# Sheet2.net
KiCad netlist of a schematic drawn in Altium Designer
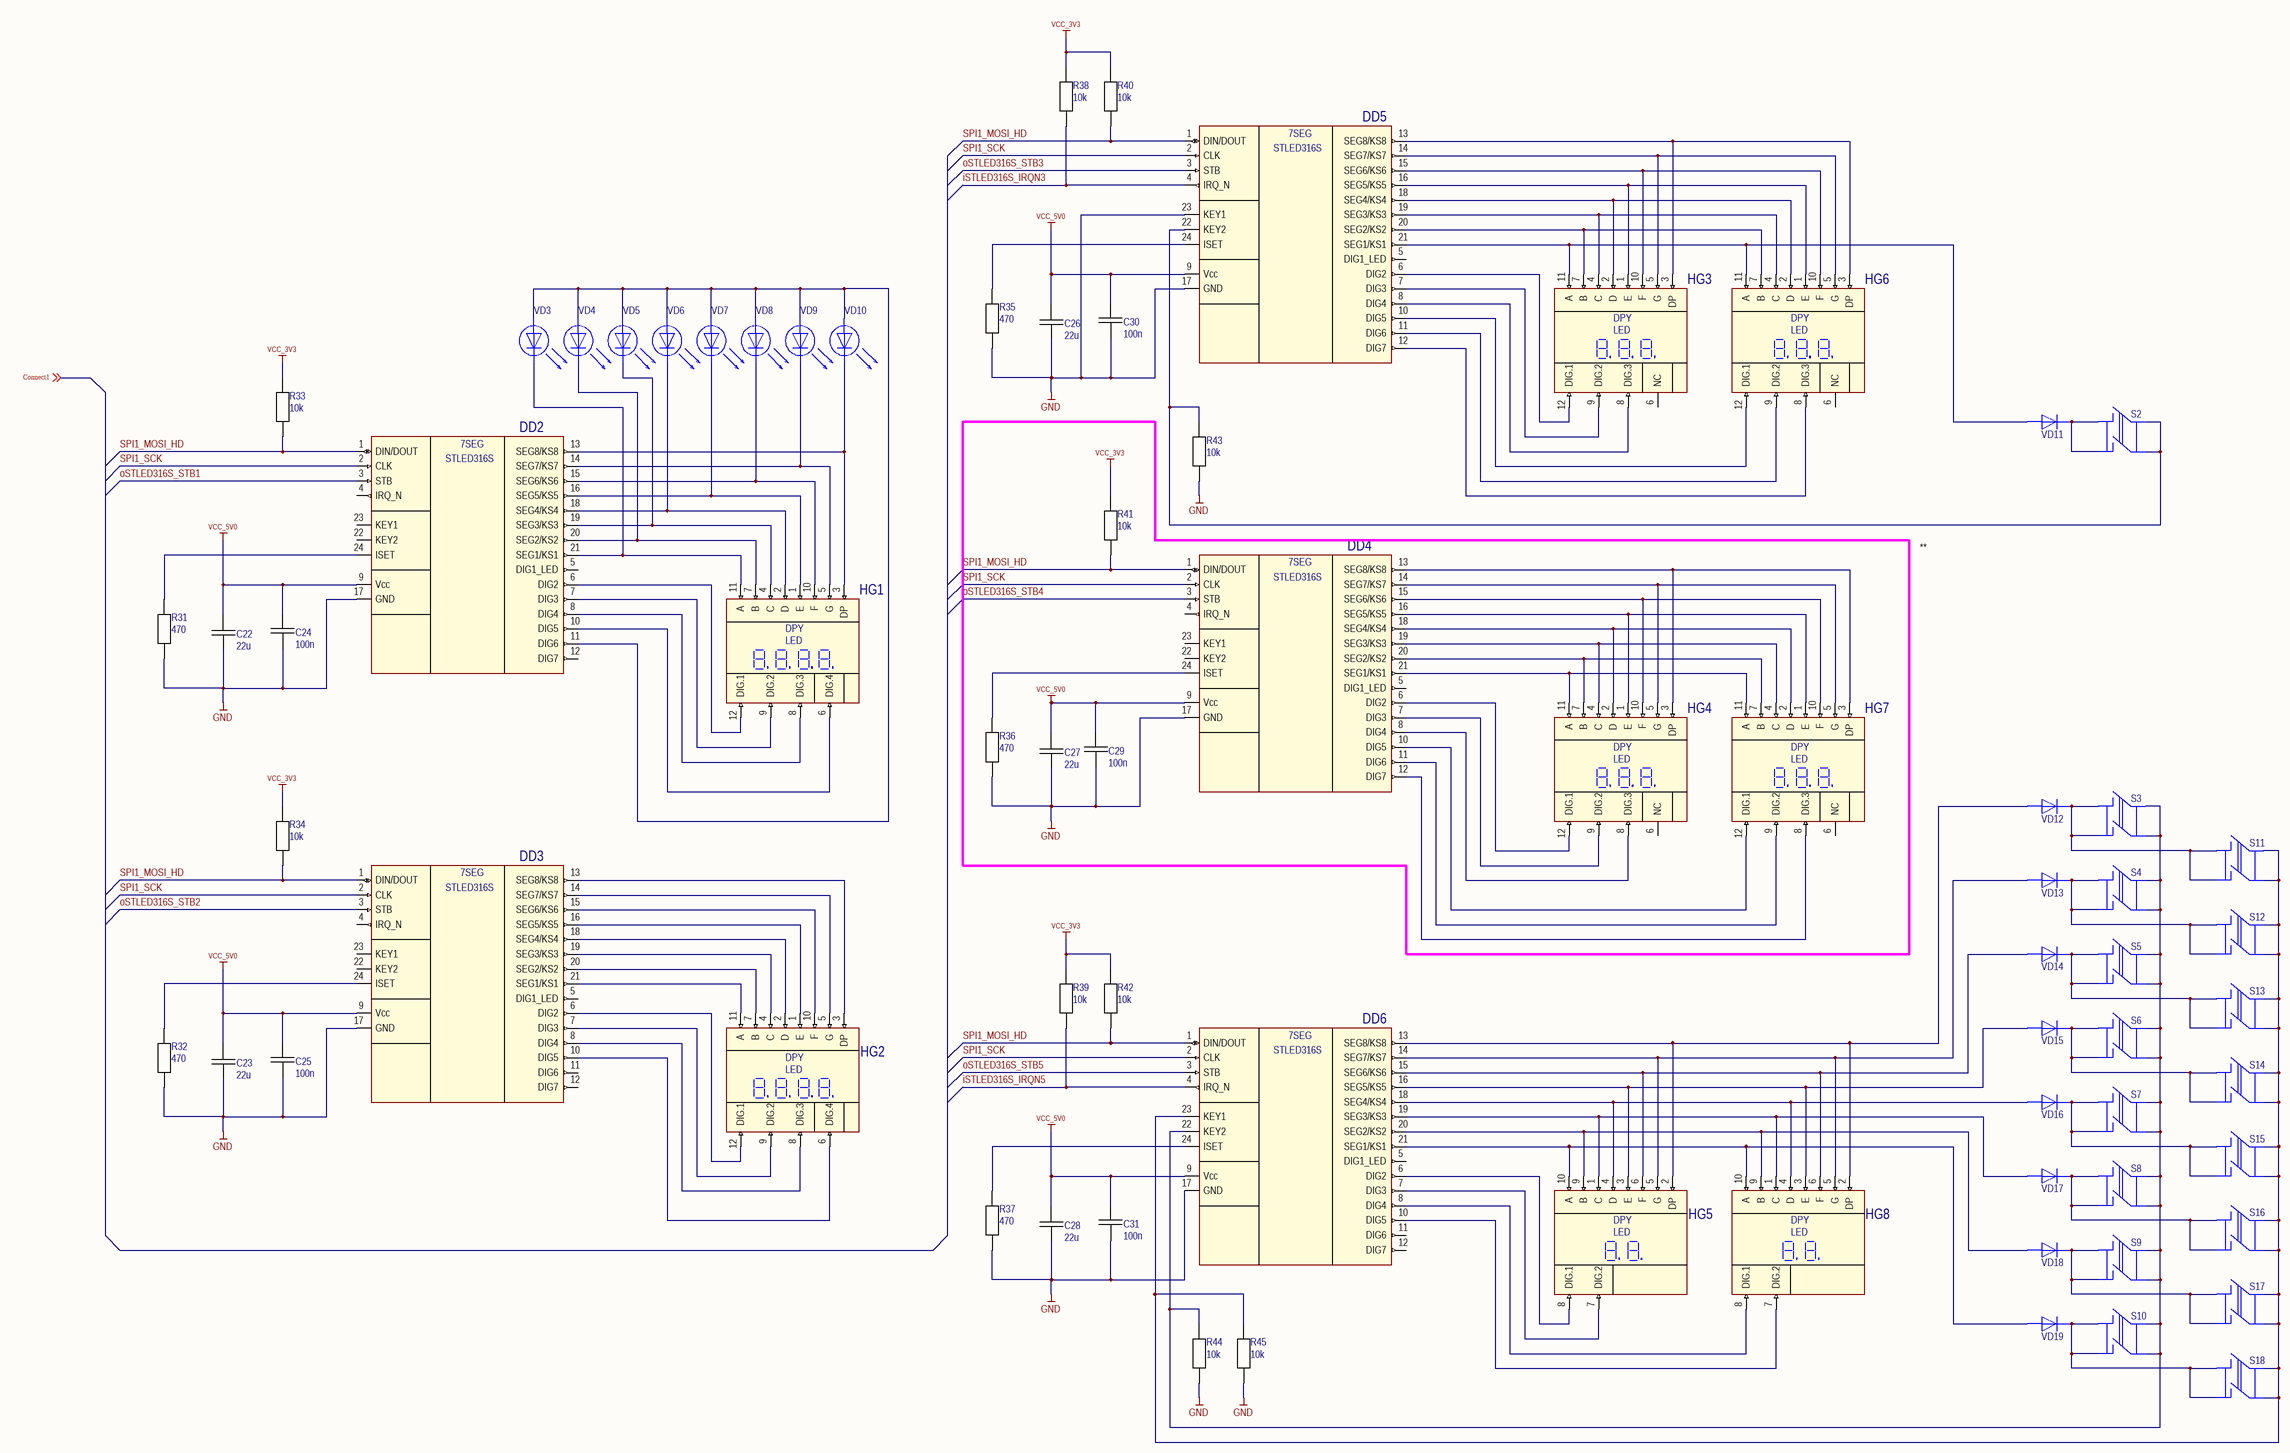
[diagram p0: Sheet2.SchDoc]

(export (version "E")
  (design (tool "Eeschema 10.0.6"))
  (components
    (comp (ref "C22")
      (value "22u")
      (footprint "CAPACITOR_1206")
      (libsource (lib "Библиотека элементов") (part "Capacitor_1206"))
    )
    (comp (ref "C23")
      (value "22u")
      (footprint "CAPACITOR_1206")
      (libsource (lib "Библиотека элементов") (part "Capacitor_1206"))
    )
    (comp (ref "C24")
      (value "100n")
      (footprint "Capacitor_0805")
      (libsource (lib "Библиотека элементов") (part "Capacitor_0805"))
    )
    (comp (ref "C25")
      (value "100n")
      (footprint "Capacitor_0805")
      (libsource (lib "Библиотека элементов") (part "Capacitor_0805"))
    )
    (comp (ref "C26")
      (value "22u")
      (footprint "CAPACITOR_1206")
      (libsource (lib "Библиотека элементов") (part "Capacitor_1206"))
    )
    (comp (ref "C27")
      (value "22u")
      (footprint "CAPACITOR_1206")
      (libsource (lib "Библиотека элементов") (part "Capacitor_1206"))
    )
    (comp (ref "C28")
      (value "22u")
      (footprint "CAPACITOR_1206")
      (libsource (lib "Библиотека элементов") (part "Capacitor_1206"))
    )
    (comp (ref "C29")
      (value "100n")
      (footprint "Capacitor_0805")
      (libsource (lib "Библиотека элементов") (part "Capacitor_0805"))
    )
    (comp (ref "C30")
      (value "100n")
      (footprint "Capacitor_0805")
      (libsource (lib "Библиотека элементов") (part "Capacitor_0805"))
    )
    (comp (ref "C31")
      (value "100n")
      (footprint "Capacitor_0805")
      (libsource (lib "Библиотека элементов") (part "Capacitor_0805"))
    )
    (comp (ref "DD2")
      (value "STLED316S")
      (footprint "SO-24")
      (libsource (lib "Библиотека элементов") (part "STLED316S"))
    )
    (comp (ref "DD3")
      (value "STLED316S")
      (footprint "SO-24")
      (libsource (lib "Библиотека элементов") (part "STLED316S"))
    )
    (comp (ref "DD4")
      (value "STLED316S")
      (footprint "SO-24")
      (libsource (lib "Библиотека элементов") (part "STLED316S"))
    )
    (comp (ref "DD5")
      (value "STLED316S")
      (footprint "SO-24")
      (libsource (lib "Библиотека элементов") (part "STLED316S"))
    )
    (comp (ref "DD6")
      (value "STLED316S")
      (footprint "SO-24")
      (libsource (lib "Библиотека элементов") (part "STLED316S"))
    )
    (comp (ref "HG1")
      (value "FYQ-5641BG-21")
      (footprint "FYQ-5641BG-21")
      (libsource (lib "Библиотека элементов") (part "FYQ-5641BG-21"))
    )
    (comp (ref "HG2")
      (value "FYQ-5641BG-21")
      (footprint "FYQ-5641BG-21")
      (libsource (lib "Библиотека элементов") (part "FYQ-5641BG-21"))
    )
    (comp (ref "HG3")
      (value "FYT-5631Bx")
      (footprint "FYT-5631Bx")
      (libsource (lib "Библиотека элементов") (part "FYT-5631Bx"))
    )
    (comp (ref "HG4") (value "FYT-5631Bx") (libsource (lib "Библиотека элементов") (part "FYT-5631Bx")))
    (comp (ref "HG5")
      (value "FYD-5621Bx")
      (footprint "FYD-5621Bx")
      (libsource (lib "Библиотека элементов") (part "FYD-5621Bx"))
    )
    (comp (ref "HG6")
      (value "FYT-5631Bx")
      (footprint "FYT-5631Bx")
      (libsource (lib "Библиотека элементов") (part "FYT-5631Bx"))
    )
    (comp (ref "HG7") (value "FYT-5631Bx") (libsource (lib "Библиотека элементов") (part "FYT-5631Bx")))
    (comp (ref "HG8")
      (value "FYD-5621Bx")
      (footprint "FYD-5621Bx")
      (libsource (lib "Библиотека элементов") (part "FYD-5621Bx"))
    )
    (comp (ref "R31")
      (value "470")
      (footprint "RESISTOR_SMD0805")
      (libsource (lib "Библиотека элементов") (part "Resistor_0805"))
    )
    (comp (ref "R32")
      (value "470")
      (footprint "RESISTOR_SMD0805")
      (libsource (lib "Библиотека элементов") (part "Resistor_0805"))
    )
    (comp (ref "R33")
      (value "10k")
      (footprint "RESISTOR_SMD0805")
      (libsource (lib "Библиотека элементов") (part "Resistor_0805"))
    )
    (comp (ref "R34")
      (value "10k")
      (footprint "RESISTOR_SMD0805")
      (libsource (lib "Библиотека элементов") (part "Resistor_0805"))
    )
    (comp (ref "R35")
      (value "470")
      (footprint "RESISTOR_SMD0805")
      (libsource (lib "Библиотека элементов") (part "Resistor_0805"))
    )
    (comp (ref "R36")
      (value "470")
      (footprint "RESISTOR_SMD0805")
      (libsource (lib "Библиотека элементов") (part "Resistor_0805"))
    )
    (comp (ref "R37")
      (value "470")
      (footprint "RESISTOR_SMD0805")
      (libsource (lib "Библиотека элементов") (part "Resistor_0805"))
    )
    (comp (ref "R38")
      (value "10k")
      (footprint "RESISTOR_SMD0805")
      (libsource (lib "Библиотека элементов") (part "Resistor_0805"))
    )
    (comp (ref "R39")
      (value "10k")
      (footprint "RESISTOR_SMD0805")
      (libsource (lib "Библиотека элементов") (part "Resistor_0805"))
    )
    (comp (ref "R40")
      (value "10k")
      (footprint "RESISTOR_SMD0805")
      (libsource (lib "Библиотека элементов") (part "Resistor_0805"))
    )
    (comp (ref "R41")
      (value "10k")
      (footprint "RESISTOR_SMD0805")
      (libsource (lib "Библиотека элементов") (part "Resistor_0805"))
    )
    (comp (ref "R42")
      (value "10k")
      (footprint "RESISTOR_SMD0805")
      (libsource (lib "Библиотека элементов") (part "Resistor_0805"))
    )
    (comp (ref "R43")
      (value "10k")
      (footprint "RESISTOR_SMD0805")
      (libsource (lib "Библиотека элементов") (part "Resistor_0805"))
    )
    (comp (ref "R44")
      (value "10k")
      (footprint "RESISTOR_SMD0805")
      (libsource (lib "Библиотека элементов") (part "Resistor_0805"))
    )
    (comp (ref "R45")
      (value "10k")
      (footprint "RESISTOR_SMD0805")
      (libsource (lib "Библиотека элементов") (part "Resistor_0805"))
    )
    (comp (ref "S2")
      (value "DTS-26 12x12x9.5")
      (footprint "Tact Switch_DTS-26_12x12x95")
      (libsource (lib "Библиотека элементов") (part "Tact_Switch_DTS-26_12x12x95"))
    )
    (comp (ref "S3")
      (value "DTS-26 12x12x9.5")
      (footprint "Tact Switch_DTS-26_12x12x95")
      (libsource (lib "Библиотека элементов") (part "Tact_Switch_DTS-26_12x12x95"))
    )
    (comp (ref "S4")
      (value "DTS-26 12x12x9.5")
      (footprint "Tact Switch_DTS-26_12x12x95")
      (libsource (lib "Библиотека элементов") (part "Tact_Switch_DTS-26_12x12x95"))
    )
    (comp (ref "S5")
      (value "DTS-26 12x12x9.5")
      (footprint "Tact Switch_DTS-26_12x12x95")
      (libsource (lib "Библиотека элементов") (part "Tact_Switch_DTS-26_12x12x95"))
    )
    (comp (ref "S6")
      (value "DTS-26 12x12x9.5")
      (footprint "Tact Switch_DTS-26_12x12x95")
      (libsource (lib "Библиотека элементов") (part "Tact_Switch_DTS-26_12x12x95"))
    )
    (comp (ref "S7")
      (value "DTS-26 12x12x9.5")
      (footprint "Tact Switch_DTS-26_12x12x95")
      (libsource (lib "Библиотека элементов") (part "Tact_Switch_DTS-26_12x12x95"))
    )
    (comp (ref "S8")
      (value "DTS-26 12x12x9.5")
      (footprint "Tact Switch_DTS-26_12x12x95")
      (libsource (lib "Библиотека элементов") (part "Tact_Switch_DTS-26_12x12x95"))
    )
    (comp (ref "S9")
      (value "DTS-26 12x12x9.5")
      (footprint "Tact Switch_DTS-26_12x12x95")
      (libsource (lib "Библиотека элементов") (part "Tact_Switch_DTS-26_12x12x95"))
    )
    (comp (ref "S10")
      (value "DTS-26 12x12x9.5")
      (footprint "Tact Switch_DTS-26_12x12x95")
      (libsource (lib "Библиотека элементов") (part "Tact_Switch_DTS-26_12x12x95"))
    )
    (comp (ref "S11")
      (value "DTS-26 12x12x9.5")
      (footprint "Tact Switch_DTS-26_12x12x95")
      (libsource (lib "Библиотека элементов") (part "Tact_Switch_DTS-26_12x12x95"))
    )
    (comp (ref "S12")
      (value "DTS-26 12x12x9.5")
      (footprint "Tact Switch_DTS-26_12x12x95")
      (libsource (lib "Библиотека элементов") (part "Tact_Switch_DTS-26_12x12x95"))
    )
    (comp (ref "S13")
      (value "DTS-26 12x12x9.5")
      (footprint "Tact Switch_DTS-26_12x12x95")
      (libsource (lib "Библиотека элементов") (part "Tact_Switch_DTS-26_12x12x95"))
    )
    (comp (ref "S14")
      (value "DTS-26 12x12x9.5")
      (footprint "Tact Switch_DTS-26_12x12x95")
      (libsource (lib "Библиотека элементов") (part "Tact_Switch_DTS-26_12x12x95"))
    )
    (comp (ref "S15")
      (value "DTS-26 12x12x9.5")
      (footprint "Tact Switch_DTS-26_12x12x95")
      (libsource (lib "Библиотека элементов") (part "Tact_Switch_DTS-26_12x12x95"))
    )
    (comp (ref "S16")
      (value "DTS-26 12x12x9.5")
      (footprint "Tact Switch_DTS-26_12x12x95")
      (libsource (lib "Библиотека элементов") (part "Tact_Switch_DTS-26_12x12x95"))
    )
    (comp (ref "S17")
      (value "DTS-26 12x12x9.5")
      (footprint "Tact Switch_DTS-26_12x12x95")
      (libsource (lib "Библиотека элементов") (part "Tact_Switch_DTS-26_12x12x95"))
    )
    (comp (ref "S18")
      (value "DTS-26 12x12x9.5")
      (footprint "Tact Switch_DTS-26_12x12x95")
      (libsource (lib "Библиотека элементов") (part "Tact_Switch_DTS-26_12x12x95"))
    )
    (comp (ref "VD3")
      (value "LED_FYL-3014GD1A")
      (libsource (lib "Библиотека элементов") (part "LED_FYL-3014GD1A"))
    )
    (comp (ref "VD4")
      (value "LED_FYL-3014GD1A")
      (libsource (lib "Библиотека элементов") (part "LED_FYL-3014GD1A"))
    )
    (comp (ref "VD5")
      (value "LED_FYL-3014GD1A")
      (libsource (lib "Библиотека элементов") (part "LED_FYL-3014GD1A"))
    )
    (comp (ref "VD6")
      (value "LED_FYL-3014GD1A")
      (libsource (lib "Библиотека элементов") (part "LED_FYL-3014GD1A"))
    )
    (comp (ref "VD7")
      (value "LED_FYL-3014GD1A")
      (footprint "LED_ FYL-3014GD1A")
      (libsource (lib "Библиотека элементов") (part "LED_FYL-3014GD1A"))
    )
    (comp (ref "VD8")
      (value "LED_FYL-3014GD1A")
      (footprint "LED_ FYL-3014GD1A")
      (libsource (lib "Библиотека элементов") (part "LED_FYL-3014GD1A"))
    )
    (comp (ref "VD9")
      (value "LED_FYL-3014GD1A")
      (footprint "LED_ FYL-3014GD1A")
      (libsource (lib "Библиотека элементов") (part "LED_FYL-3014GD1A"))
    )
    (comp (ref "VD10")
      (value "LED_FYL-3014GD1A")
      (footprint "LED_ FYL-3014GD1A")
      (libsource (lib "Библиотека элементов") (part "LED_FYL-3014GD1A"))
    )
    (comp (ref "VD11")
      (value "MMSD4148")
      (footprint "Diode_MMSD4148")
      (libsource (lib "Библиотека элементов") (part "Diode_MMSD4148"))
    )
    (comp (ref "VD12")
      (value "MMSD4148")
      (footprint "Diode_MMSD4148")
      (libsource (lib "Библиотека элементов") (part "Diode_MMSD4148"))
    )
    (comp (ref "VD13")
      (value "MMSD4148")
      (footprint "Diode_MMSD4148")
      (libsource (lib "Библиотека элементов") (part "Diode_MMSD4148"))
    )
    (comp (ref "VD14")
      (value "MMSD4148")
      (footprint "Diode_MMSD4148")
      (libsource (lib "Библиотека элементов") (part "Diode_MMSD4148"))
    )
    (comp (ref "VD15")
      (value "MMSD4148")
      (footprint "Diode_MMSD4148")
      (libsource (lib "Библиотека элементов") (part "Diode_MMSD4148"))
    )
    (comp (ref "VD16")
      (value "MMSD4148")
      (footprint "Diode_MMSD4148")
      (libsource (lib "Библиотека элементов") (part "Diode_MMSD4148"))
    )
    (comp (ref "VD17")
      (value "MMSD4148")
      (footprint "Diode_MMSD4148")
      (libsource (lib "Библиотека элементов") (part "Diode_MMSD4148"))
    )
    (comp (ref "VD18")
      (value "MMSD4148")
      (footprint "Diode_MMSD4148")
      (libsource (lib "Библиотека элементов") (part "Diode_MMSD4148"))
    )
    (comp (ref "VD19")
      (value "MMSD4148")
      (footprint "Diode_MMSD4148")
      (libsource (lib "Библиотека элементов") (part "Diode_MMSD4148"))
    )
  )
  (nets
    (net (code "1") (name "/SPI1_MOSI_HD") (class "Default")
      (node (ref "DD2") (pin "1") (pinfunction "DIN/DOUT_1") (pintype "bidirectional"))
      (node (ref "DD3") (pin "1") (pinfunction "DIN/DOUT_1") (pintype "bidirectional"))
      (node (ref "DD4") (pin "1") (pinfunction "DIN/DOUT_1") (pintype "bidirectional"))
      (node (ref "DD5") (pin "1") (pinfunction "DIN/DOUT_1") (pintype "bidirectional"))
      (node (ref "DD6") (pin "1") (pinfunction "DIN/DOUT_1") (pintype "bidirectional"))
      (node (ref "R33") (pin "1") (pinfunction "1_1") (pintype "passive"))
      (node (ref "R34") (pin "1") (pinfunction "1_1") (pintype "passive"))
      (node (ref "R40") (pin "1") (pinfunction "1_1") (pintype "passive"))
      (node (ref "R41") (pin "1") (pinfunction "1_1") (pintype "passive"))
      (node (ref "R42") (pin "1") (pinfunction "1_1") (pintype "passive"))
    )
    (net (code "2") (name "/SPI1_SCK") (class "Default")
      (node (ref "DD2") (pin "2") (pinfunction "CLK_2") (pintype "input"))
      (node (ref "DD3") (pin "2") (pinfunction "CLK_2") (pintype "input"))
      (node (ref "DD4") (pin "2") (pinfunction "CLK_2") (pintype "input"))
      (node (ref "DD5") (pin "2") (pinfunction "CLK_2") (pintype "input"))
      (node (ref "DD6") (pin "2") (pinfunction "CLK_2") (pintype "input"))
    )
    (net (code "3") (name "/iSTLED316S_IRQN3") (class "Default")
      (node (ref "DD5") (pin "4") (pinfunction "IRQ_N_4") (pintype "output"))
      (node (ref "R38") (pin "1") (pinfunction "1_1") (pintype "passive"))
    )
    (net (code "4") (name "/iSTLED316S_IRQN5") (class "Default")
      (node (ref "DD6") (pin "4") (pinfunction "IRQ_N_4") (pintype "output"))
      (node (ref "R39") (pin "1") (pinfunction "1_1") (pintype "passive"))
    )
    (net (code "5") (name "/oSTLED316S_STB1") (class "Default")
      (node (ref "DD2") (pin "3") (pinfunction "STB_3") (pintype "input"))
    )
    (net (code "6") (name "/oSTLED316S_STB2") (class "Default")
      (node (ref "DD3") (pin "3") (pinfunction "STB_3") (pintype "input"))
    )
    (net (code "7") (name "/oSTLED316S_STB3") (class "Default")
      (node (ref "DD5") (pin "3") (pinfunction "STB_3") (pintype "input"))
    )
    (net (code "8") (name "/oSTLED316S_STB4") (class "Default")
      (node (ref "DD4") (pin "3") (pinfunction "STB_3") (pintype "input"))
    )
    (net (code "9") (name "/oSTLED316S_STB5") (class "Default")
      (node (ref "DD6") (pin "3") (pinfunction "STB_3") (pintype "input"))
    )
    (net (code "11") (name "GND") (class "Default")
      (node (ref "C22") (pin "2") (pinfunction "2_2") (pintype "passive"))
      (node (ref "C23") (pin "2") (pinfunction "2_2") (pintype "passive"))
      (node (ref "C24") (pin "1") (pinfunction "1_1") (pintype "passive"))
      (node (ref "C25") (pin "1") (pinfunction "1_1") (pintype "passive"))
      (node (ref "C26") (pin "2") (pinfunction "2_2") (pintype "passive"))
      (node (ref "C27") (pin "2") (pinfunction "2_2") (pintype "passive"))
      (node (ref "C28") (pin "2") (pinfunction "2_2") (pintype "passive"))
      (node (ref "C29") (pin "1") (pinfunction "1_1") (pintype "passive"))
      (node (ref "C30") (pin "1") (pinfunction "1_1") (pintype "passive"))
      (node (ref "C31") (pin "1") (pinfunction "1_1") (pintype "passive"))
      (node (ref "DD2") (pin "17") (pinfunction "GND_17") (pintype "power_in"))
      (node (ref "DD3") (pin "17") (pinfunction "GND_17") (pintype "power_in"))
      (node (ref "DD4") (pin "17") (pinfunction "GND_17") (pintype "power_in"))
      (node (ref "DD5") (pin "17") (pinfunction "GND_17") (pintype "power_in"))
      (node (ref "DD5") (pin "23") (pinfunction "KEY1_23") (pintype "passive"))
      (node (ref "DD6") (pin "17") (pinfunction "GND_17") (pintype "power_in"))
      (node (ref "R31") (pin "1") (pinfunction "1_1") (pintype "passive"))
      (node (ref "R32") (pin "1") (pinfunction "1_1") (pintype "passive"))
      (node (ref "R35") (pin "1") (pinfunction "1_1") (pintype "passive"))
      (node (ref "R36") (pin "1") (pinfunction "1_1") (pintype "passive"))
      (node (ref "R37") (pin "1") (pinfunction "1_1") (pintype "passive"))
      (node (ref "R43") (pin "1") (pinfunction "1_1") (pintype "passive"))
      (node (ref "R44") (pin "1") (pinfunction "1_1") (pintype "passive"))
      (node (ref "R45") (pin "1") (pinfunction "1_1") (pintype "passive"))
    )
    (net (code "12") (name "Net-(DD2-DIG2)") (class "Default")
      (node (ref "DD2") (pin "6") (pinfunction "DIG2_6") (pintype "output"))
      (node (ref "HG1") (pin "12") (pinfunction "DIG.1_12") (pintype "input"))
    )
    (net (code "13") (name "Net-(DD2-DIG3)") (class "Default")
      (node (ref "DD2") (pin "7") (pinfunction "DIG3_7") (pintype "output"))
      (node (ref "HG1") (pin "9") (pinfunction "DIG.2_9") (pintype "input"))
    )
    (net (code "14") (name "Net-(DD2-DIG4)") (class "Default")
      (node (ref "DD2") (pin "8") (pinfunction "DIG4_8") (pintype "output"))
      (node (ref "HG1") (pin "8") (pinfunction "DIG.3_8") (pintype "input"))
    )
    (net (code "15") (name "Net-(DD2-DIG5)") (class "Default")
      (node (ref "DD2") (pin "10") (pinfunction "DIG5_10") (pintype "output"))
      (node (ref "HG1") (pin "6") (pinfunction "DIG.4_6") (pintype "input"))
    )
    (net (code "16") (name "Net-(DD2-DIG6)") (class "Default")
      (node (ref "DD2") (pin "11") (pinfunction "DIG6_11") (pintype "output"))
      (node (ref "VD10") (pin "2") (pinfunction "2_2") (pintype "passive"))
      (node (ref "VD3") (pin "2") (pinfunction "2_2") (pintype "passive"))
      (node (ref "VD4") (pin "2") (pinfunction "2_2") (pintype "passive"))
      (node (ref "VD5") (pin "2") (pinfunction "2_2") (pintype "passive"))
      (node (ref "VD6") (pin "2") (pinfunction "2_2") (pintype "passive"))
      (node (ref "VD7") (pin "2") (pinfunction "2_2") (pintype "passive"))
      (node (ref "VD8") (pin "2") (pinfunction "2_2") (pintype "passive"))
      (node (ref "VD9") (pin "2") (pinfunction "2_2") (pintype "passive"))
    )
    (net (code "17") (name "Net-(DD2-ISET)") (class "Default")
      (node (ref "DD2") (pin "24") (pinfunction "ISET_24") (pintype "passive"))
      (node (ref "R31") (pin "2") (pinfunction "2_2") (pintype "passive"))
    )
    (net (code "18") (name "Net-(DD2-SEG1{slash}KS1)") (class "Default")
      (node (ref "DD2") (pin "21") (pinfunction "SEG1/KS1_21") (pintype "output"))
      (node (ref "HG1") (pin "11") (pinfunction "A_11") (pintype "input"))
      (node (ref "VD3") (pin "1") (pinfunction "1_1") (pintype "passive"))
    )
    (net (code "19") (name "Net-(DD2-SEG2{slash}KS2)") (class "Default")
      (node (ref "DD2") (pin "20") (pinfunction "SEG2/KS2_20") (pintype "output"))
      (node (ref "HG1") (pin "7") (pinfunction "B_7") (pintype "input"))
      (node (ref "VD4") (pin "1") (pinfunction "1_1") (pintype "passive"))
    )
    (net (code "20") (name "Net-(DD2-SEG3{slash}KS3)") (class "Default")
      (node (ref "DD2") (pin "19") (pinfunction "SEG3/KS3_19") (pintype "output"))
      (node (ref "HG1") (pin "4") (pinfunction "C_4") (pintype "input"))
      (node (ref "VD5") (pin "1") (pinfunction "1_1") (pintype "passive"))
    )
    (net (code "21") (name "Net-(DD2-SEG4{slash}KS4)") (class "Default")
      (node (ref "DD2") (pin "18") (pinfunction "SEG4/KS4_18") (pintype "output"))
      (node (ref "HG1") (pin "2") (pinfunction "D_2") (pintype "input"))
      (node (ref "VD6") (pin "1") (pinfunction "1_1") (pintype "passive"))
    )
    (net (code "22") (name "Net-(DD2-SEG5{slash}KS5)") (class "Default")
      (node (ref "DD2") (pin "16") (pinfunction "SEG5/KS5_16") (pintype "output"))
      (node (ref "HG1") (pin "1") (pinfunction "E_1") (pintype "input"))
      (node (ref "VD7") (pin "1") (pinfunction "1_1") (pintype "passive"))
    )
    (net (code "23") (name "Net-(DD2-SEG6{slash}KS6)") (class "Default")
      (node (ref "DD2") (pin "15") (pinfunction "SEG6/KS6_15") (pintype "output"))
      (node (ref "HG1") (pin "10") (pinfunction "F_10") (pintype "input"))
      (node (ref "VD8") (pin "1") (pinfunction "1_1") (pintype "passive"))
    )
    (net (code "24") (name "Net-(DD2-SEG7{slash}KS7)") (class "Default")
      (node (ref "DD2") (pin "14") (pinfunction "SEG7/KS7_14") (pintype "output"))
      (node (ref "HG1") (pin "5") (pinfunction "G_5") (pintype "input"))
      (node (ref "VD9") (pin "1") (pinfunction "1_1") (pintype "passive"))
    )
    (net (code "25") (name "Net-(DD2-SEG8{slash}KS8)") (class "Default")
      (node (ref "DD2") (pin "13") (pinfunction "SEG8/KS8_13") (pintype "output"))
      (node (ref "HG1") (pin "3") (pinfunction "DP_3") (pintype "input"))
      (node (ref "VD10") (pin "1") (pinfunction "1_1") (pintype "passive"))
    )
    (net (code "26") (name "Net-(DD3-DIG2)") (class "Default")
      (node (ref "DD3") (pin "6") (pinfunction "DIG2_6") (pintype "output"))
      (node (ref "HG2") (pin "12") (pinfunction "DIG.1_12") (pintype "input"))
    )
    (net (code "27") (name "Net-(DD3-DIG3)") (class "Default")
      (node (ref "DD3") (pin "7") (pinfunction "DIG3_7") (pintype "output"))
      (node (ref "HG2") (pin "9") (pinfunction "DIG.2_9") (pintype "input"))
    )
    (net (code "28") (name "Net-(DD3-DIG4)") (class "Default")
      (node (ref "DD3") (pin "8") (pinfunction "DIG4_8") (pintype "output"))
      (node (ref "HG2") (pin "8") (pinfunction "DIG.3_8") (pintype "input"))
    )
    (net (code "29") (name "Net-(DD3-DIG5)") (class "Default")
      (node (ref "DD3") (pin "10") (pinfunction "DIG5_10") (pintype "output"))
      (node (ref "HG2") (pin "6") (pinfunction "DIG.4_6") (pintype "input"))
    )
    (net (code "30") (name "Net-(DD3-ISET)") (class "Default")
      (node (ref "DD3") (pin "24") (pinfunction "ISET_24") (pintype "passive"))
      (node (ref "R32") (pin "2") (pinfunction "2_2") (pintype "passive"))
    )
    (net (code "31") (name "Net-(DD3-SEG1{slash}KS1)") (class "Default")
      (node (ref "DD3") (pin "21") (pinfunction "SEG1/KS1_21") (pintype "output"))
      (node (ref "HG2") (pin "11") (pinfunction "A_11") (pintype "input"))
    )
    (net (code "32") (name "Net-(DD3-SEG2{slash}KS2)") (class "Default")
      (node (ref "DD3") (pin "20") (pinfunction "SEG2/KS2_20") (pintype "output"))
      (node (ref "HG2") (pin "7") (pinfunction "B_7") (pintype "input"))
    )
    (net (code "33") (name "Net-(DD3-SEG3{slash}KS3)") (class "Default")
      (node (ref "DD3") (pin "19") (pinfunction "SEG3/KS3_19") (pintype "output"))
      (node (ref "HG2") (pin "4") (pinfunction "C_4") (pintype "input"))
    )
    (net (code "34") (name "Net-(DD3-SEG4{slash}KS4)") (class "Default")
      (node (ref "DD3") (pin "18") (pinfunction "SEG4/KS4_18") (pintype "output"))
      (node (ref "HG2") (pin "2") (pinfunction "D_2") (pintype "input"))
    )
    (net (code "35") (name "Net-(DD3-SEG5{slash}KS5)") (class "Default")
      (node (ref "DD3") (pin "16") (pinfunction "SEG5/KS5_16") (pintype "output"))
      (node (ref "HG2") (pin "1") (pinfunction "E_1") (pintype "input"))
    )
    (net (code "36") (name "Net-(DD3-SEG6{slash}KS6)") (class "Default")
      (node (ref "DD3") (pin "15") (pinfunction "SEG6/KS6_15") (pintype "output"))
      (node (ref "HG2") (pin "10") (pinfunction "F_10") (pintype "input"))
    )
    (net (code "37") (name "Net-(DD3-SEG7{slash}KS7)") (class "Default")
      (node (ref "DD3") (pin "14") (pinfunction "SEG7/KS7_14") (pintype "output"))
      (node (ref "HG2") (pin "5") (pinfunction "G_5") (pintype "input"))
    )
    (net (code "38") (name "Net-(DD3-SEG8{slash}KS8)") (class "Default")
      (node (ref "DD3") (pin "13") (pinfunction "SEG8/KS8_13") (pintype "output"))
      (node (ref "HG2") (pin "3") (pinfunction "DP_3") (pintype "input"))
    )
    (net (code "39") (name "Net-(DD4-DIG2)") (class "Default")
      (node (ref "DD4") (pin "6") (pinfunction "DIG2_6") (pintype "output"))
      (node (ref "HG4") (pin "12") (pinfunction "DIG.1_12") (pintype "input"))
    )
    (net (code "40") (name "Net-(DD4-DIG3)") (class "Default")
      (node (ref "DD4") (pin "7") (pinfunction "DIG3_7") (pintype "output"))
      (node (ref "HG4") (pin "9") (pinfunction "DIG.2_9") (pintype "input"))
    )
    (net (code "41") (name "Net-(DD4-DIG4)") (class "Default")
      (node (ref "DD4") (pin "8") (pinfunction "DIG4_8") (pintype "output"))
      (node (ref "HG4") (pin "8") (pinfunction "DIG.3_8") (pintype "input"))
    )
    (net (code "42") (name "Net-(DD4-DIG5)") (class "Default")
      (node (ref "DD4") (pin "10") (pinfunction "DIG5_10") (pintype "output"))
      (node (ref "HG7") (pin "12") (pinfunction "DIG.1_12") (pintype "input"))
    )
    (net (code "43") (name "Net-(DD4-DIG6)") (class "Default")
      (node (ref "DD4") (pin "11") (pinfunction "DIG6_11") (pintype "output"))
      (node (ref "HG7") (pin "9") (pinfunction "DIG.2_9") (pintype "input"))
    )
    (net (code "44") (name "Net-(DD4-DIG7)") (class "Default")
      (node (ref "DD4") (pin "12") (pinfunction "DIG7_12") (pintype "output"))
      (node (ref "HG7") (pin "8") (pinfunction "DIG.3_8") (pintype "input"))
    )
    (net (code "45") (name "Net-(DD4-ISET)") (class "Default")
      (node (ref "DD4") (pin "24") (pinfunction "ISET_24") (pintype "passive"))
      (node (ref "R36") (pin "2") (pinfunction "2_2") (pintype "passive"))
    )
    (net (code "46") (name "Net-(DD4-SEG1{slash}KS1)") (class "Default")
      (node (ref "DD4") (pin "21") (pinfunction "SEG1/KS1_21") (pintype "output"))
      (node (ref "HG4") (pin "11") (pinfunction "A_11") (pintype "input"))
      (node (ref "HG7") (pin "11") (pinfunction "A_11") (pintype "input"))
    )
    (net (code "47") (name "Net-(DD4-SEG2{slash}KS2)") (class "Default")
      (node (ref "DD4") (pin "20") (pinfunction "SEG2/KS2_20") (pintype "output"))
      (node (ref "HG4") (pin "7") (pinfunction "B_7") (pintype "input"))
      (node (ref "HG7") (pin "7") (pinfunction "B_7") (pintype "input"))
    )
    (net (code "48") (name "Net-(DD4-SEG3{slash}KS3)") (class "Default")
      (node (ref "DD4") (pin "19") (pinfunction "SEG3/KS3_19") (pintype "output"))
      (node (ref "HG4") (pin "4") (pinfunction "C_4") (pintype "input"))
      (node (ref "HG7") (pin "4") (pinfunction "C_4") (pintype "input"))
    )
    (net (code "49") (name "Net-(DD4-SEG4{slash}KS4)") (class "Default")
      (node (ref "DD4") (pin "18") (pinfunction "SEG4/KS4_18") (pintype "output"))
      (node (ref "HG4") (pin "2") (pinfunction "D_2") (pintype "input"))
      (node (ref "HG7") (pin "2") (pinfunction "D_2") (pintype "input"))
    )
    (net (code "50") (name "Net-(DD4-SEG5{slash}KS5)") (class "Default")
      (node (ref "DD4") (pin "16") (pinfunction "SEG5/KS5_16") (pintype "output"))
      (node (ref "HG4") (pin "1") (pinfunction "E_1") (pintype "input"))
      (node (ref "HG7") (pin "1") (pinfunction "E_1") (pintype "input"))
    )
    (net (code "51") (name "Net-(DD4-SEG6{slash}KS6)") (class "Default")
      (node (ref "DD4") (pin "15") (pinfunction "SEG6/KS6_15") (pintype "output"))
      (node (ref "HG4") (pin "10") (pinfunction "F_10") (pintype "input"))
      (node (ref "HG7") (pin "10") (pinfunction "F_10") (pintype "input"))
    )
    (net (code "52") (name "Net-(DD4-SEG7{slash}KS7)") (class "Default")
      (node (ref "DD4") (pin "14") (pinfunction "SEG7/KS7_14") (pintype "output"))
      (node (ref "HG4") (pin "5") (pinfunction "G_5") (pintype "input"))
      (node (ref "HG7") (pin "5") (pinfunction "G_5") (pintype "input"))
    )
    (net (code "53") (name "Net-(DD4-SEG8{slash}KS8)") (class "Default")
      (node (ref "DD4") (pin "13") (pinfunction "SEG8/KS8_13") (pintype "output"))
      (node (ref "HG4") (pin "3") (pinfunction "DP_3") (pintype "input"))
      (node (ref "HG7") (pin "3") (pinfunction "DP_3") (pintype "input"))
    )
    (net (code "54") (name "Net-(DD5-DIG2)") (class "Default")
      (node (ref "DD5") (pin "6") (pinfunction "DIG2_6") (pintype "output"))
      (node (ref "HG3") (pin "12") (pinfunction "DIG.1_12") (pintype "input"))
    )
    (net (code "55") (name "Net-(DD5-DIG3)") (class "Default")
      (node (ref "DD5") (pin "7") (pinfunction "DIG3_7") (pintype "output"))
      (node (ref "HG3") (pin "9") (pinfunction "DIG.2_9") (pintype "input"))
    )
    (net (code "56") (name "Net-(DD5-DIG4)") (class "Default")
      (node (ref "DD5") (pin "8") (pinfunction "DIG4_8") (pintype "output"))
      (node (ref "HG3") (pin "8") (pinfunction "DIG.3_8") (pintype "input"))
    )
    (net (code "57") (name "Net-(DD5-DIG5)") (class "Default")
      (node (ref "DD5") (pin "10") (pinfunction "DIG5_10") (pintype "output"))
      (node (ref "HG6") (pin "12") (pinfunction "DIG.1_12") (pintype "input"))
    )
    (net (code "58") (name "Net-(DD5-DIG6)") (class "Default")
      (node (ref "DD5") (pin "11") (pinfunction "DIG6_11") (pintype "output"))
      (node (ref "HG6") (pin "9") (pinfunction "DIG.2_9") (pintype "input"))
    )
    (net (code "59") (name "Net-(DD5-DIG7)") (class "Default")
      (node (ref "DD5") (pin "12") (pinfunction "DIG7_12") (pintype "output"))
      (node (ref "HG6") (pin "8") (pinfunction "DIG.3_8") (pintype "input"))
    )
    (net (code "60") (name "Net-(DD5-ISET)") (class "Default")
      (node (ref "DD5") (pin "24") (pinfunction "ISET_24") (pintype "passive"))
      (node (ref "R35") (pin "2") (pinfunction "2_2") (pintype "passive"))
    )
    (net (code "61") (name "Net-(DD5-KEY2)") (class "Default")
      (node (ref "DD5") (pin "22") (pinfunction "KEY2_22") (pintype "passive"))
      (node (ref "R43") (pin "2") (pinfunction "2_2") (pintype "passive"))
      (node (ref "S2") (pin "3") (pintype "passive"))
      (node (ref "S2") (pin "4") (pintype "passive"))
    )
    (net (code "62") (name "Net-(DD5-SEG1{slash}KS1)") (class "Default")
      (node (ref "DD5") (pin "21") (pinfunction "SEG1/KS1_21") (pintype "output"))
      (node (ref "HG3") (pin "11") (pinfunction "A_11") (pintype "input"))
      (node (ref "HG6") (pin "11") (pinfunction "A_11") (pintype "input"))
      (node (ref "VD11") (pin "2") (pinfunction "2_2") (pintype "passive"))
    )
    (net (code "63") (name "Net-(DD5-SEG2{slash}KS2)") (class "Default")
      (node (ref "DD5") (pin "20") (pinfunction "SEG2/KS2_20") (pintype "output"))
      (node (ref "HG3") (pin "7") (pinfunction "B_7") (pintype "input"))
      (node (ref "HG6") (pin "7") (pinfunction "B_7") (pintype "input"))
    )
    (net (code "64") (name "Net-(DD5-SEG3{slash}KS3)") (class "Default")
      (node (ref "DD5") (pin "19") (pinfunction "SEG3/KS3_19") (pintype "output"))
      (node (ref "HG3") (pin "4") (pinfunction "C_4") (pintype "input"))
      (node (ref "HG6") (pin "4") (pinfunction "C_4") (pintype "input"))
    )
    (net (code "65") (name "Net-(DD5-SEG4{slash}KS4)") (class "Default")
      (node (ref "DD5") (pin "18") (pinfunction "SEG4/KS4_18") (pintype "output"))
      (node (ref "HG3") (pin "2") (pinfunction "D_2") (pintype "input"))
      (node (ref "HG6") (pin "2") (pinfunction "D_2") (pintype "input"))
    )
    (net (code "66") (name "Net-(DD5-SEG5{slash}KS5)") (class "Default")
      (node (ref "DD5") (pin "16") (pinfunction "SEG5/KS5_16") (pintype "output"))
      (node (ref "HG3") (pin "1") (pinfunction "E_1") (pintype "input"))
      (node (ref "HG6") (pin "1") (pinfunction "E_1") (pintype "input"))
    )
    (net (code "67") (name "Net-(DD5-SEG6{slash}KS6)") (class "Default")
      (node (ref "DD5") (pin "15") (pinfunction "SEG6/KS6_15") (pintype "output"))
      (node (ref "HG3") (pin "10") (pinfunction "F_10") (pintype "input"))
      (node (ref "HG6") (pin "10") (pinfunction "F_10") (pintype "input"))
    )
    (net (code "68") (name "Net-(DD5-SEG7{slash}KS7)") (class "Default")
      (node (ref "DD5") (pin "14") (pinfunction "SEG7/KS7_14") (pintype "output"))
      (node (ref "HG3") (pin "5") (pinfunction "G_5") (pintype "input"))
      (node (ref "HG6") (pin "5") (pinfunction "G_5") (pintype "input"))
    )
    (net (code "69") (name "Net-(DD5-SEG8{slash}KS8)") (class "Default")
      (node (ref "DD5") (pin "13") (pinfunction "SEG8/KS8_13") (pintype "output"))
      (node (ref "HG3") (pin "3") (pinfunction "DP_3") (pintype "input"))
      (node (ref "HG6") (pin "3") (pinfunction "DP_3") (pintype "input"))
    )
    (net (code "70") (name "Net-(DD6-DIG2)") (class "Default")
      (node (ref "DD6") (pin "6") (pinfunction "DIG2_6") (pintype "output"))
      (node (ref "HG5") (pin "8") (pinfunction "DIG.1_8") (pintype "input"))
    )
    (net (code "71") (name "Net-(DD6-DIG3)") (class "Default")
      (node (ref "DD6") (pin "7") (pinfunction "DIG3_7") (pintype "output"))
      (node (ref "HG5") (pin "7") (pinfunction "DIG.2_7") (pintype "input"))
    )
    (net (code "72") (name "Net-(DD6-DIG4)") (class "Default")
      (node (ref "DD6") (pin "8") (pinfunction "DIG4_8") (pintype "output"))
      (node (ref "HG8") (pin "8") (pinfunction "DIG.1_8") (pintype "input"))
    )
    (net (code "73") (name "Net-(DD6-DIG5)") (class "Default")
      (node (ref "DD6") (pin "10") (pinfunction "DIG5_10") (pintype "output"))
      (node (ref "HG8") (pin "7") (pinfunction "DIG.2_7") (pintype "input"))
    )
    (net (code "74") (name "Net-(DD6-ISET)") (class "Default")
      (node (ref "DD6") (pin "24") (pinfunction "ISET_24") (pintype "passive"))
      (node (ref "R37") (pin "2") (pinfunction "2_2") (pintype "passive"))
    )
    (net (code "75") (name "Net-(DD6-KEY1)") (class "Default")
      (node (ref "DD6") (pin "23") (pinfunction "KEY1_23") (pintype "passive"))
      (node (ref "R45") (pin "2") (pinfunction "2_2") (pintype "passive"))
      (node (ref "S11") (pin "3") (pintype "passive"))
      (node (ref "S11") (pin "4") (pintype "passive"))
      (node (ref "S12") (pin "3") (pintype "passive"))
      (node (ref "S12") (pin "4") (pintype "passive"))
      (node (ref "S13") (pin "3") (pintype "passive"))
      (node (ref "S13") (pin "4") (pintype "passive"))
      (node (ref "S14") (pin "3") (pintype "passive"))
      (node (ref "S14") (pin "4") (pintype "passive"))
      (node (ref "S15") (pin "3") (pintype "passive"))
      (node (ref "S15") (pin "4") (pintype "passive"))
      (node (ref "S16") (pin "3") (pintype "passive"))
      (node (ref "S16") (pin "4") (pintype "passive"))
      (node (ref "S17") (pin "3") (pintype "passive"))
      (node (ref "S17") (pin "4") (pintype "passive"))
      (node (ref "S18") (pin "3") (pintype "passive"))
      (node (ref "S18") (pin "4") (pintype "passive"))
    )
    (net (code "76") (name "Net-(DD6-KEY2)") (class "Default")
      (node (ref "DD6") (pin "22") (pinfunction "KEY2_22") (pintype "passive"))
      (node (ref "R44") (pin "2") (pinfunction "2_2") (pintype "passive"))
      (node (ref "S10") (pin "3") (pintype "passive"))
      (node (ref "S10") (pin "4") (pintype "passive"))
      (node (ref "S3") (pin "3") (pintype "passive"))
      (node (ref "S3") (pin "4") (pintype "passive"))
      (node (ref "S4") (pin "3") (pintype "passive"))
      (node (ref "S4") (pin "4") (pintype "passive"))
      (node (ref "S5") (pin "3") (pintype "passive"))
      (node (ref "S5") (pin "4") (pintype "passive"))
      (node (ref "S6") (pin "3") (pintype "passive"))
      (node (ref "S6") (pin "4") (pintype "passive"))
      (node (ref "S7") (pin "3") (pintype "passive"))
      (node (ref "S7") (pin "4") (pintype "passive"))
      (node (ref "S8") (pin "3") (pintype "passive"))
      (node (ref "S8") (pin "4") (pintype "passive"))
      (node (ref "S9") (pin "3") (pintype "passive"))
      (node (ref "S9") (pin "4") (pintype "passive"))
    )
    (net (code "77") (name "Net-(DD6-SEG1{slash}KS1)") (class "Default")
      (node (ref "DD6") (pin "21") (pinfunction "SEG1/KS1_21") (pintype "output"))
      (node (ref "HG5") (pin "10") (pinfunction "A_10") (pintype "input"))
      (node (ref "HG8") (pin "10") (pinfunction "A_10") (pintype "input"))
      (node (ref "VD19") (pin "2") (pinfunction "2_2") (pintype "passive"))
    )
    (net (code "78") (name "Net-(DD6-SEG2{slash}KS2)") (class "Default")
      (node (ref "DD6") (pin "20") (pinfunction "SEG2/KS2_20") (pintype "output"))
      (node (ref "HG5") (pin "9") (pinfunction "B_9") (pintype "input"))
      (node (ref "HG8") (pin "9") (pinfunction "B_9") (pintype "input"))
      (node (ref "VD18") (pin "2") (pinfunction "2_2") (pintype "passive"))
    )
    (net (code "79") (name "Net-(DD6-SEG3{slash}KS3)") (class "Default")
      (node (ref "DD6") (pin "19") (pinfunction "SEG3/KS3_19") (pintype "output"))
      (node (ref "HG5") (pin "1") (pinfunction "C_1") (pintype "input"))
      (node (ref "HG8") (pin "1") (pinfunction "C_1") (pintype "input"))
      (node (ref "VD17") (pin "2") (pinfunction "2_2") (pintype "passive"))
    )
    (net (code "80") (name "Net-(DD6-SEG4{slash}KS4)") (class "Default")
      (node (ref "DD6") (pin "18") (pinfunction "SEG4/KS4_18") (pintype "output"))
      (node (ref "HG5") (pin "4") (pinfunction "D_4") (pintype "input"))
      (node (ref "HG8") (pin "4") (pinfunction "D_4") (pintype "input"))
      (node (ref "VD16") (pin "2") (pinfunction "2_2") (pintype "passive"))
    )
    (net (code "81") (name "Net-(DD6-SEG5{slash}KS5)") (class "Default")
      (node (ref "DD6") (pin "16") (pinfunction "SEG5/KS5_16") (pintype "output"))
      (node (ref "HG5") (pin "3") (pinfunction "E_3") (pintype "input"))
      (node (ref "HG8") (pin "3") (pinfunction "E_3") (pintype "input"))
      (node (ref "VD15") (pin "2") (pinfunction "2_2") (pintype "passive"))
    )
    (net (code "82") (name "Net-(DD6-SEG6{slash}KS6)") (class "Default")
      (node (ref "DD6") (pin "15") (pinfunction "SEG6/KS6_15") (pintype "output"))
      (node (ref "HG5") (pin "6") (pinfunction "F_6") (pintype "input"))
      (node (ref "HG8") (pin "6") (pinfunction "F_6") (pintype "input"))
      (node (ref "VD14") (pin "2") (pinfunction "2_2") (pintype "passive"))
    )
    (net (code "83") (name "Net-(DD6-SEG7{slash}KS7)") (class "Default")
      (node (ref "DD6") (pin "14") (pinfunction "SEG7/KS7_14") (pintype "output"))
      (node (ref "HG5") (pin "5") (pinfunction "G_5") (pintype "input"))
      (node (ref "HG8") (pin "5") (pinfunction "G_5") (pintype "input"))
      (node (ref "VD13") (pin "2") (pinfunction "2_2") (pintype "passive"))
    )
    (net (code "84") (name "Net-(DD6-SEG8{slash}KS8)") (class "Default")
      (node (ref "DD6") (pin "13") (pinfunction "SEG8/KS8_13") (pintype "output"))
      (node (ref "HG5") (pin "2") (pinfunction "DP_2") (pintype "input"))
      (node (ref "HG8") (pin "2") (pinfunction "DP_2") (pintype "input"))
      (node (ref "VD12") (pin "2") (pinfunction "2_2") (pintype "passive"))
    )
    (net (code "85") (name "Net-(S2-Pad1)") (class "Default")
      (node (ref "S2") (pin "1") (pintype "passive"))
      (node (ref "S2") (pin "2") (pintype "passive"))
      (node (ref "VD11") (pin "1") (pinfunction "1_1") (pintype "passive"))
    )
    (net (code "86") (name "Net-(S10-Pad1)") (class "Default")
      (node (ref "S10") (pin "1") (pintype "passive"))
      (node (ref "S10") (pin "2") (pintype "passive"))
      (node (ref "S18") (pin "1") (pintype "passive"))
      (node (ref "S18") (pin "2") (pintype "passive"))
      (node (ref "VD19") (pin "1") (pinfunction "1_1") (pintype "passive"))
    )
    (net (code "87") (name "Net-(S11-Pad1)") (class "Default")
      (node (ref "S11") (pin "1") (pintype "passive"))
      (node (ref "S11") (pin "2") (pintype "passive"))
      (node (ref "S3") (pin "1") (pintype "passive"))
      (node (ref "S3") (pin "2") (pintype "passive"))
      (node (ref "VD12") (pin "1") (pinfunction "1_1") (pintype "passive"))
    )
    (net (code "88") (name "Net-(S12-Pad1)") (class "Default")
      (node (ref "S12") (pin "1") (pintype "passive"))
      (node (ref "S12") (pin "2") (pintype "passive"))
      (node (ref "S4") (pin "1") (pintype "passive"))
      (node (ref "S4") (pin "2") (pintype "passive"))
      (node (ref "VD13") (pin "1") (pinfunction "1_1") (pintype "passive"))
    )
    (net (code "89") (name "Net-(S13-Pad1)") (class "Default")
      (node (ref "S13") (pin "1") (pintype "passive"))
      (node (ref "S13") (pin "2") (pintype "passive"))
      (node (ref "S5") (pin "1") (pintype "passive"))
      (node (ref "S5") (pin "2") (pintype "passive"))
      (node (ref "VD14") (pin "1") (pinfunction "1_1") (pintype "passive"))
    )
    (net (code "90") (name "Net-(S14-Pad1)") (class "Default")
      (node (ref "S14") (pin "1") (pintype "passive"))
      (node (ref "S14") (pin "2") (pintype "passive"))
      (node (ref "S6") (pin "1") (pintype "passive"))
      (node (ref "S6") (pin "2") (pintype "passive"))
      (node (ref "VD15") (pin "1") (pinfunction "1_1") (pintype "passive"))
    )
    (net (code "91") (name "Net-(S15-Pad1)") (class "Default")
      (node (ref "S15") (pin "1") (pintype "passive"))
      (node (ref "S15") (pin "2") (pintype "passive"))
      (node (ref "S7") (pin "1") (pintype "passive"))
      (node (ref "S7") (pin "2") (pintype "passive"))
      (node (ref "VD16") (pin "1") (pinfunction "1_1") (pintype "passive"))
    )
    (net (code "92") (name "Net-(S16-Pad1)") (class "Default")
      (node (ref "S16") (pin "1") (pintype "passive"))
      (node (ref "S16") (pin "2") (pintype "passive"))
      (node (ref "S8") (pin "1") (pintype "passive"))
      (node (ref "S8") (pin "2") (pintype "passive"))
      (node (ref "VD17") (pin "1") (pinfunction "1_1") (pintype "passive"))
    )
    (net (code "93") (name "Net-(S17-Pad1)") (class "Default")
      (node (ref "S17") (pin "1") (pintype "passive"))
      (node (ref "S17") (pin "2") (pintype "passive"))
      (node (ref "S9") (pin "1") (pintype "passive"))
      (node (ref "S9") (pin "2") (pintype "passive"))
      (node (ref "VD18") (pin "1") (pinfunction "1_1") (pintype "passive"))
    )
    (net (code "94") (name "VCC_3V3") (class "Default")
      (node (ref "R33") (pin "2") (pinfunction "2_2") (pintype "passive"))
      (node (ref "R34") (pin "2") (pinfunction "2_2") (pintype "passive"))
      (node (ref "R38") (pin "2") (pinfunction "2_2") (pintype "passive"))
      (node (ref "R39") (pin "2") (pinfunction "2_2") (pintype "passive"))
      (node (ref "R40") (pin "2") (pinfunction "2_2") (pintype "passive"))
      (node (ref "R41") (pin "2") (pinfunction "2_2") (pintype "passive"))
      (node (ref "R42") (pin "2") (pinfunction "2_2") (pintype "passive"))
    )
    (net (code "95") (name "VCC_5V0") (class "Default")
      (node (ref "C22") (pin "1") (pinfunction "1_1") (pintype "passive"))
      (node (ref "C23") (pin "1") (pinfunction "1_1") (pintype "passive"))
      (node (ref "C24") (pin "2") (pinfunction "2_2") (pintype "passive"))
      (node (ref "C25") (pin "2") (pinfunction "2_2") (pintype "passive"))
      (node (ref "C26") (pin "1") (pinfunction "1_1") (pintype "passive"))
      (node (ref "C27") (pin "1") (pinfunction "1_1") (pintype "passive"))
      (node (ref "C28") (pin "1") (pinfunction "1_1") (pintype "passive"))
      (node (ref "C29") (pin "2") (pinfunction "2_2") (pintype "passive"))
      (node (ref "C30") (pin "2") (pinfunction "2_2") (pintype "passive"))
      (node (ref "C31") (pin "2") (pinfunction "2_2") (pintype "passive"))
      (node (ref "DD2") (pin "9") (pinfunction "Vcc_9") (pintype "power_in"))
      (node (ref "DD3") (pin "9") (pinfunction "Vcc_9") (pintype "power_in"))
      (node (ref "DD4") (pin "9") (pinfunction "Vcc_9") (pintype "power_in"))
      (node (ref "DD5") (pin "9") (pinfunction "Vcc_9") (pintype "power_in"))
      (node (ref "DD6") (pin "9") (pinfunction "Vcc_9") (pintype "power_in"))
    )
    (net (code "96") (name "unconnected-(DD2-DIG1_LED-Pad5)") (class "Default")
      (node (ref "DD2") (pin "5") (pinfunction "DIG1_LED_5") (pintype "output"))
    )
    (net (code "97") (name "unconnected-(DD2-DIG7-Pad12)") (class "Default")
      (node (ref "DD2") (pin "12") (pinfunction "DIG7_12") (pintype "output"))
    )
    (net (code "98") (name "unconnected-(DD2-IRQ_N-Pad4)") (class "Default")
      (node (ref "DD2") (pin "4") (pinfunction "IRQ_N_4") (pintype "output"))
    )
    (net (code "99") (name "unconnected-(DD2-KEY1-Pad23)") (class "Default")
      (node (ref "DD2") (pin "23") (pinfunction "KEY1_23") (pintype "passive"))
    )
    (net (code "100") (name "unconnected-(DD2-KEY2-Pad22)") (class "Default")
      (node (ref "DD2") (pin "22") (pinfunction "KEY2_22") (pintype "passive"))
    )
    (net (code "101") (name "unconnected-(DD3-DIG1_LED-Pad5)") (class "Default")
      (node (ref "DD3") (pin "5") (pinfunction "DIG1_LED_5") (pintype "output"))
    )
    (net (code "102") (name "unconnected-(DD3-DIG6-Pad11)") (class "Default")
      (node (ref "DD3") (pin "11") (pinfunction "DIG6_11") (pintype "output"))
    )
    (net (code "103") (name "unconnected-(DD3-DIG7-Pad12)") (class "Default")
      (node (ref "DD3") (pin "12") (pinfunction "DIG7_12") (pintype "output"))
    )
    (net (code "104") (name "unconnected-(DD3-IRQ_N-Pad4)") (class "Default")
      (node (ref "DD3") (pin "4") (pinfunction "IRQ_N_4") (pintype "output"))
    )
    (net (code "105") (name "unconnected-(DD3-KEY1-Pad23)") (class "Default")
      (node (ref "DD3") (pin "23") (pinfunction "KEY1_23") (pintype "passive"))
    )
    (net (code "106") (name "unconnected-(DD3-KEY2-Pad22)") (class "Default")
      (node (ref "DD3") (pin "22") (pinfunction "KEY2_22") (pintype "passive"))
    )
    (net (code "107") (name "unconnected-(DD4-DIG1_LED-Pad5)") (class "Default")
      (node (ref "DD4") (pin "5") (pinfunction "DIG1_LED_5") (pintype "output"))
    )
    (net (code "108") (name "unconnected-(DD4-IRQ_N-Pad4)") (class "Default")
      (node (ref "DD4") (pin "4") (pinfunction "IRQ_N_4") (pintype "output"))
    )
    (net (code "109") (name "unconnected-(DD4-KEY1-Pad23)") (class "Default")
      (node (ref "DD4") (pin "23") (pinfunction "KEY1_23") (pintype "passive"))
    )
    (net (code "110") (name "unconnected-(DD4-KEY2-Pad22)") (class "Default")
      (node (ref "DD4") (pin "22") (pinfunction "KEY2_22") (pintype "passive"))
    )
    (net (code "111") (name "unconnected-(DD5-DIG1_LED-Pad5)") (class "Default")
      (node (ref "DD5") (pin "5") (pinfunction "DIG1_LED_5") (pintype "output"))
    )
    (net (code "112") (name "unconnected-(DD6-DIG1_LED-Pad5)") (class "Default")
      (node (ref "DD6") (pin "5") (pinfunction "DIG1_LED_5") (pintype "output"))
    )
    (net (code "113") (name "unconnected-(DD6-DIG6-Pad11)") (class "Default")
      (node (ref "DD6") (pin "11") (pinfunction "DIG6_11") (pintype "output"))
    )
    (net (code "114") (name "unconnected-(DD6-DIG7-Pad12)") (class "Default")
      (node (ref "DD6") (pin "12") (pinfunction "DIG7_12") (pintype "output"))
    )
    (net (code "115") (name "unconnected-(HG3-NC-Pad6)") (class "Default")
      (node (ref "HG3") (pin "6") (pinfunction "NC_6") (pintype "passive"))
    )
    (net (code "116") (name "unconnected-(HG4-NC-Pad6)") (class "Default")
      (node (ref "HG4") (pin "6") (pinfunction "NC_6") (pintype "passive"))
    )
    (net (code "117") (name "unconnected-(HG6-NC-Pad6)") (class "Default")
      (node (ref "HG6") (pin "6") (pinfunction "NC_6") (pintype "passive"))
    )
    (net (code "118") (name "unconnected-(HG7-NC-Pad6)") (class "Default")
      (node (ref "HG7") (pin "6") (pinfunction "NC_6") (pintype "passive"))
    )
  )
)
